# H-Bridge_V_2A.net
KiCad netlist of a schematic drawn in EAGLE
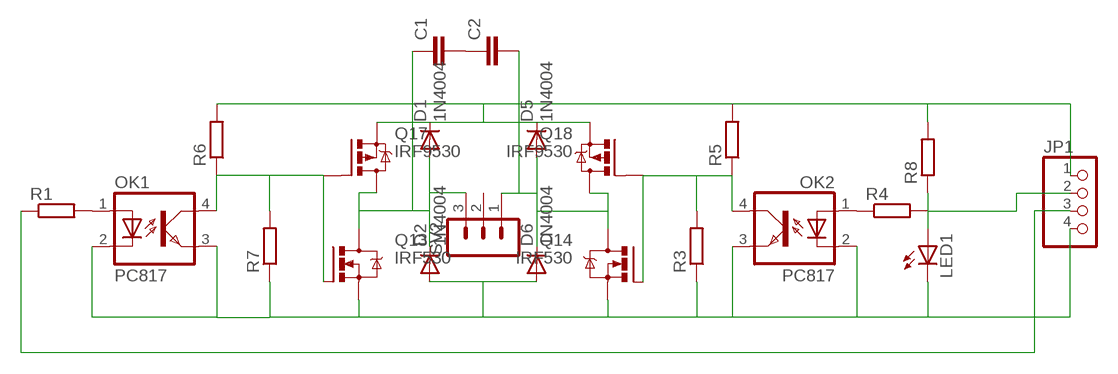
[diagram p0: schematic, sheet 1]

(export (version "E")
  (design (tool "Eeschema 10.0.6"))
  (components
    (comp (ref "C1")
      (value "C-EU025-025X050")
      (footprint "eagle-import:C025-025X050")
      (libsource (lib "eagle-import") (part "C-EU025-025X050"))
    )
    (comp (ref "C2")
      (value "C-EU025-025X050")
      (footprint "eagle-import:C025-025X050")
      (libsource (lib "eagle-import") (part "C-EU025-025X050"))
    )
    (comp (ref "D1")
      (value "1N4004")
      (footprint "eagle-import:DO41-10")
      (libsource (lib "eagle-import") (part "1N4004"))
    )
    (comp (ref "D2")
      (value "1N4004")
      (footprint "eagle-import:DO41-10")
      (libsource (lib "eagle-import") (part "1N4004"))
    )
    (comp (ref "D5")
      (value "1N4004")
      (footprint "eagle-import:DO41-10")
      (libsource (lib "eagle-import") (part "1N4004"))
    )
    (comp (ref "D6")
      (value "1N4004")
      (footprint "eagle-import:DO41-10")
      (libsource (lib "eagle-import") (part "1N4004"))
    )
    (comp (ref "JP1")
      (value "PINHD-1X4")
      (footprint "eagle-import:1X04")
      (libsource (lib "eagle-import") (part "PINHD-1X4"))
    )
    (comp (ref "LED1")
      (value "LED3MM")
      (footprint "eagle-import:LED3MM")
      (libsource (lib "eagle-import") (part "LED3MM"))
    )
    (comp (ref "OK1")
      (value "PC817")
      (footprint "eagle-import:DIL04")
      (fields (field (name "MPN") "PC817X4J000F"))
      (libsource (lib "eagle-import") (part "PC817"))
    )
    (comp (ref "OK2")
      (value "PC817")
      (footprint "eagle-import:DIL04")
      (fields (field (name "MPN") "PC817X4J000F"))
      (libsource (lib "eagle-import") (part "PC817"))
    )
    (comp (ref "Q13")
      (value "IRF530")
      (footprint "eagle-import:TO220BV")
      (libsource (lib "eagle-import") (part "IRF530"))
    )
    (comp (ref "Q14")
      (value "IRF530")
      (footprint "eagle-import:TO220BV")
      (libsource (lib "eagle-import") (part "IRF530"))
    )
    (comp (ref "Q17")
      (value "IRF9530")
      (footprint "eagle-import:TO220BV")
      (libsource (lib "eagle-import") (part "IRF9530"))
    )
    (comp (ref "Q18")
      (value "IRF9530")
      (footprint "eagle-import:TO220BV")
      (libsource (lib "eagle-import") (part "IRF9530"))
    )
    (comp (ref "R1")
      (value "R-EU_0207/10")
      (footprint "eagle-import:0207_10")
      (libsource (lib "eagle-import") (part "R-EU_0207/10"))
    )
    (comp (ref "R3")
      (value "R-EU_0204/7")
      (footprint "eagle-import:0204_7")
      (libsource (lib "eagle-import") (part "R-EU_0204/7"))
    )
    (comp (ref "R4")
      (value "R-EU_0207/10")
      (footprint "eagle-import:0207_10")
      (libsource (lib "eagle-import") (part "R-EU_0207/10"))
    )
    (comp (ref "R5")
      (value "R-EU_0207/10")
      (footprint "eagle-import:0207_10")
      (libsource (lib "eagle-import") (part "R-EU_0207/10"))
    )
    (comp (ref "R6")
      (value "R-EU_0207/10")
      (footprint "eagle-import:0207_10")
      (libsource (lib "eagle-import") (part "R-EU_0207/10"))
    )
    (comp (ref "R7")
      (value "R-EU_0204/7")
      (footprint "eagle-import:0204_7")
      (libsource (lib "eagle-import") (part "R-EU_0204/7"))
    )
    (comp (ref "R8")
      (value "R-EU_0207/10")
      (footprint "eagle-import:0207_10")
      (libsource (lib "eagle-import") (part "R-EU_0207/10"))
    )
    (comp (ref "SV2")
      (value "MA03-1")
      (footprint "eagle-import:MA03-1")
      (libsource (lib "eagle-import") (part "MA03-1"))
    )
  )
  (nets
    (net (code "1") (name "Net-(C1-Pad1)") (class "Default")
      (node (ref "C1") (pin "1") (pinfunction "1_1") (pintype "passive"))
      (node (ref "D1") (pin "A") (pinfunction "A_A") (pintype "passive"))
      (node (ref "D2") (pin "C") (pinfunction "C_C") (pintype "passive"))
      (node (ref "Q13") (pin "D") (pinfunction "D_D") (pintype "passive"))
      (node (ref "Q17") (pin "D") (pinfunction "D_D") (pintype "passive"))
      (node (ref "SV2") (pin "3") (pinfunction "3_3") (pintype "passive"))
    )
    (net (code "2") (name "Net-(C1-Pad2)") (class "Default")
      (node (ref "C1") (pin "2") (pinfunction "2_2") (pintype "passive"))
      (node (ref "C2") (pin "1") (pinfunction "1_1") (pintype "passive"))
    )
    (net (code "3") (name "Net-(C2-Pad2)") (class "Default")
      (node (ref "C2") (pin "2") (pinfunction "2_2") (pintype "passive"))
      (node (ref "D5") (pin "A") (pinfunction "A_A") (pintype "passive"))
      (node (ref "D6") (pin "C") (pinfunction "C_C") (pintype "passive"))
      (node (ref "Q14") (pin "D") (pinfunction "D_D") (pintype "passive"))
      (node (ref "Q18") (pin "D") (pinfunction "D_D") (pintype "passive"))
      (node (ref "SV2") (pin "1") (pinfunction "1_1") (pintype "passive"))
    )
    (net (code "4") (name "Net-(D1-PadC)") (class "Default")
      (node (ref "D1") (pin "C") (pinfunction "C_C") (pintype "passive"))
      (node (ref "D5") (pin "C") (pinfunction "C_C") (pintype "passive"))
      (node (ref "JP1") (pin "1") (pinfunction "1_1") (pintype "passive"))
      (node (ref "Q17") (pin "S") (pinfunction "S_S") (pintype "passive"))
      (node (ref "Q18") (pin "S") (pinfunction "S_S") (pintype "passive"))
      (node (ref "R5") (pin "2") (pinfunction "2_2") (pintype "passive"))
      (node (ref "R6") (pin "2") (pinfunction "2_2") (pintype "passive"))
      (node (ref "R8") (pin "2") (pinfunction "2_2") (pintype "passive"))
    )
    (net (code "5") (name "Net-(JP1-Pad2)") (class "Default")
      (node (ref "JP1") (pin "2") (pinfunction "2_2") (pintype "passive"))
      (node (ref "R4") (pin "2") (pinfunction "2_2") (pintype "passive"))
    )
    (net (code "6") (name "Net-(JP1-Pad3)") (class "Default")
      (node (ref "JP1") (pin "3") (pinfunction "3_3") (pintype "passive"))
      (node (ref "R1") (pin "1") (pinfunction "1_1") (pintype "passive"))
    )
    (net (code "7") (name "Net-(LED1-C)") (class "Default")
      (node (ref "D2") (pin "A") (pinfunction "A_A") (pintype "passive"))
      (node (ref "D6") (pin "A") (pinfunction "A_A") (pintype "passive"))
      (node (ref "JP1") (pin "4") (pinfunction "4_4") (pintype "passive"))
      (node (ref "LED1") (pin "K") (pinfunction "C_K") (pintype "passive"))
      (node (ref "OK1") (pin "2") (pinfunction "C_2") (pintype "passive"))
      (node (ref "OK1") (pin "3") (pinfunction "EMIT_3") (pintype "passive"))
      (node (ref "OK2") (pin "2") (pinfunction "C_2") (pintype "passive"))
      (node (ref "OK2") (pin "3") (pinfunction "EMIT_3") (pintype "passive"))
      (node (ref "Q13") (pin "S") (pinfunction "S_S") (pintype "passive"))
      (node (ref "Q14") (pin "S") (pinfunction "S_S") (pintype "passive"))
      (node (ref "R3") (pin "1") (pinfunction "1_1") (pintype "passive"))
      (node (ref "R7") (pin "1") (pinfunction "1_1") (pintype "passive"))
    )
    (net (code "8") (name "Net-(LED1-PadA)") (class "Default")
      (node (ref "LED1") (pin "A") (pinfunction "A_A") (pintype "passive"))
      (node (ref "R8") (pin "1") (pinfunction "1_1") (pintype "passive"))
    )
    (net (code "9") (name "Net-(OK1-A)") (class "Default")
      (node (ref "OK1") (pin "1") (pinfunction "A_1") (pintype "passive"))
      (node (ref "R1") (pin "2") (pinfunction "2_2") (pintype "passive"))
    )
    (net (code "10") (name "Net-(OK1-COL)") (class "Default")
      (node (ref "OK1") (pin "4") (pinfunction "COL_4") (pintype "passive"))
      (node (ref "Q13") (pin "G") (pinfunction "G_G") (pintype "passive"))
      (node (ref "Q17") (pin "G") (pinfunction "G_G") (pintype "passive"))
      (node (ref "R6") (pin "1") (pinfunction "1_1") (pintype "passive"))
      (node (ref "R7") (pin "2") (pinfunction "2_2") (pintype "passive"))
    )
    (net (code "11") (name "Net-(OK2-A)") (class "Default")
      (node (ref "OK2") (pin "1") (pinfunction "A_1") (pintype "passive"))
      (node (ref "R4") (pin "1") (pinfunction "1_1") (pintype "passive"))
    )
    (net (code "12") (name "Net-(OK2-COL)") (class "Default")
      (node (ref "OK2") (pin "4") (pinfunction "COL_4") (pintype "passive"))
      (node (ref "Q14") (pin "G") (pinfunction "G_G") (pintype "passive"))
      (node (ref "Q18") (pin "G") (pinfunction "G_G") (pintype "passive"))
      (node (ref "R3") (pin "2") (pinfunction "2_2") (pintype "passive"))
      (node (ref "R5") (pin "1") (pinfunction "1_1") (pintype "passive"))
    )
    (net (code "13") (name "unconnected-(SV2-Pad2)") (class "Default")
      (node (ref "SV2") (pin "2") (pinfunction "2_2") (pintype "passive"))
    )
  )
)
